# ESP-VINDRIKTNING.net
KiCad netlist of a schematic drawn in EAGLE
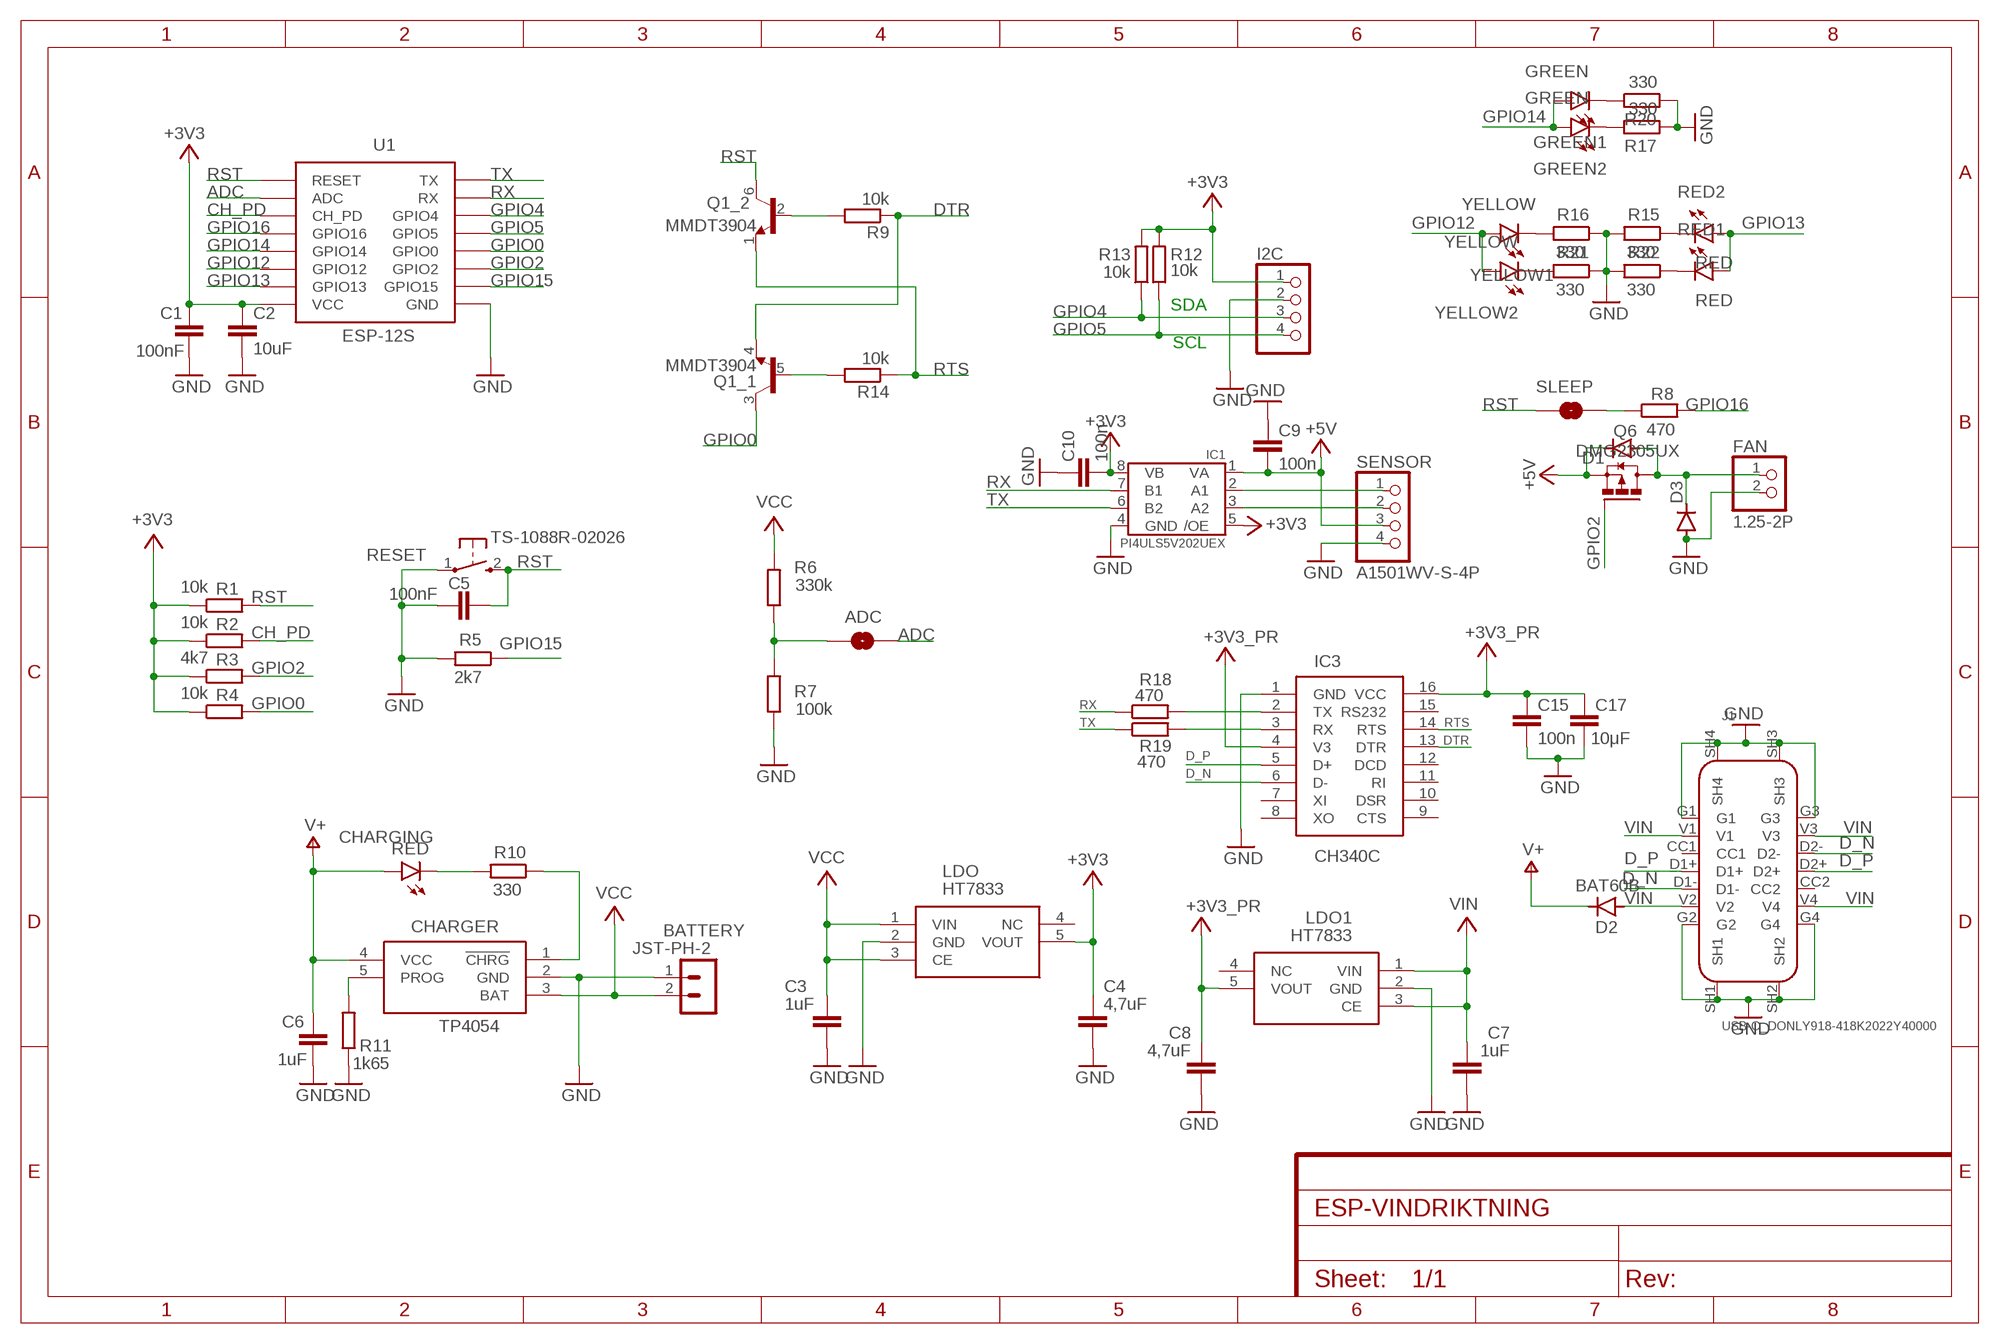
[diagram p0: schematic, sheet 1]

(export (version "E")
  (design (tool "Eeschema 10.0.6"))
  (components
    (comp (ref "ADC")
      (value "JUMPER-SMT_2_NO_NO-SILK")
      (footprint "eagle-import:SMT-JUMPER_2_NO_NO-SILK")
      (libsource (lib "eagle-import") (part "JUMPER-SMT_2_NO_NO-SILK"))
    )
    (comp (ref "BATTERY")
      (value "JST-PH-2")
      (footprint "eagle-import:B2B-PH-K")
      (libsource (lib "eagle-import") (part "JST-PH-2"))
    )
    (comp (ref "C1")
      (value "100nF")
      (footprint "eagle-import:C0603")
      (libsource (lib "eagle-import") (part "C-EUC0603"))
    )
    (comp (ref "C2")
      (value "10uF")
      (footprint "eagle-import:C0603")
      (libsource (lib "eagle-import") (part "C-EUC0603"))
    )
    (comp (ref "C3")
      (value "1uF")
      (footprint "eagle-import:C0603")
      (libsource (lib "eagle-import") (part "C-EUC0603"))
    )
    (comp (ref "C4")
      (value "4,7uF")
      (footprint "eagle-import:C0603")
      (fields (field (name "LCSC_PART") "C50936"))
      (libsource (lib "eagle-import") (part "C-EUC0603"))
    )
    (comp (ref "C5")
      (value "100nF")
      (footprint "eagle-import:C0402")
      (libsource (lib "eagle-import") (part "C-EUC0402"))
    )
    (comp (ref "C6")
      (value "1uF")
      (footprint "eagle-import:C0603")
      (libsource (lib "eagle-import") (part "C-EUC0603"))
    )
    (comp (ref "C7")
      (value "1uF")
      (footprint "eagle-import:C0603")
      (libsource (lib "eagle-import") (part "C-EUC0603"))
    )
    (comp (ref "C8")
      (value "4,7uF")
      (footprint "eagle-import:C0603")
      (fields (field (name "LCSC_PART") "C50936"))
      (libsource (lib "eagle-import") (part "C-EUC0603"))
    )
    (comp (ref "C9")
      (value "100n")
      (footprint "eagle-import:C0603")
      (libsource (lib "eagle-import") (part "C-EUC0603"))
    )
    (comp (ref "C10")
      (value "100n")
      (footprint "eagle-import:C0603")
      (libsource (lib "eagle-import") (part "C-EUC0603"))
    )
    (comp (ref "C15")
      (value "100n")
      (footprint "eagle-import:C0603")
      (libsource (lib "eagle-import") (part "C-EUC0603"))
    )
    (comp (ref "C17")
      (value "10μF")
      (footprint "eagle-import:C0603")
      (libsource (lib "eagle-import") (part "C-EUC0603"))
    )
    (comp (ref "CHARGER")
      (value "TP4054")
      (footprint "eagle-import:SOT-23-5")
      (fields (field (name "ARROW_PART_NUMBER") "TP4054-42-SOT25-R"))
      (libsource (lib "eagle-import") (part "TP4054-42-SOT25-R"))
    )
    (comp (ref "CHARGING")
      (value "RED")
      (footprint "eagle-import:CHIPLED_0603")
      (libsource (lib "eagle-import") (part "LEDCHIPLED_0603"))
    )
    (comp (ref "D1")
      (value "DIODE-SOD323-R")
      (footprint "eagle-import:SOD323-R")
      (libsource (lib "eagle-import") (part "DIODE-SOD323-R"))
    )
    (comp (ref "D2")
      (value "BAT60B")
      (footprint "eagle-import:SOD323-R")
      (libsource (lib "eagle-import") (part "DIODE-SOD323-R"))
    )
    (comp (ref "D3")
      (value "DIODE-SOD323-R")
      (footprint "eagle-import:SOD323-R")
      (libsource (lib "eagle-import") (part "DIODE-SOD323-R"))
    )
    (comp (ref "FAN")
      (value "1.25-2P")
      (footprint "eagle-import:1.25-2P")
      (fields (field (name "LCSC_PART") "C393945"))
      (libsource (lib "eagle-import") (part "1.25-2P"))
    )
    (comp (ref "GREEN1")
      (value "GREEN")
      (footprint "eagle-import:CHIP-LED0603")
      (libsource (lib "eagle-import") (part "LEDCHIP-LED0603"))
    )
    (comp (ref "GREEN2")
      (value "GREEN")
      (footprint "eagle-import:CHIP-LED0603")
      (libsource (lib "eagle-import") (part "LEDCHIP-LED0603"))
    )
    (comp (ref "I2C")
      (value "PINHD-1X4")
      (footprint "eagle-import:1X04")
      (libsource (lib "eagle-import") (part "PINHD-1X4"))
    )
    (comp (ref "IC1")
      (value "PI4ULS5V202UEX")
      (footprint "eagle-import:MSOP8")
      (fields (field (name "LCSC_PART") "C481697"))
      (libsource (lib "eagle-import") (part "PI4ULS5V202UEX"))
    )
    (comp (ref "IC3")
      (value "CH340C")
      (footprint "eagle-import:SOIC16")
      (libsource (lib "eagle-import") (part "USB_UART_CONVERTOR_CH340G"))
    )
    (comp (ref "J1")
      (value "USB-C_DONLY918-418K2022Y40000")
      (footprint "eagle-import:USB-C-TH")
      (fields (field (name "LCSC_PART") "C168704"))
      (libsource (lib "eagle-import") (part "USB-C_DONLY918-418K2022Y40000"))
    )
    (comp (ref "LDO")
      (value "HT7833")
      (footprint "eagle-import:SOT23-5")
      (libsource (lib "eagle-import") (part "HT78XX-SOT23-5SOT23-5"))
    )
    (comp (ref "LDO1")
      (value "HT7833")
      (footprint "eagle-import:SOT23-5")
      (libsource (lib "eagle-import") (part "HT78XX-SOT23-5SOT23-5"))
    )
    (comp (ref "Q1")
      (value "MMDT3904")
      (footprint "eagle-import:SC70-6")
      (fields (field (name "LCSC_PART") "C268586"))
      (libsource (lib "eagle-import") (part "TRANS_NPN_DUAL-MBT3904DW1T1"))
    )
    (comp (ref "Q6")
      (value "DMG2305UX")
      (footprint "eagle-import:SUPER-SOT3")
      (fields (field (name "LCSC_PART") "C144153"))
      (libsource (lib "eagle-import") (part "FDN360P"))
    )
    (comp (ref "R1")
      (value "10k")
      (footprint "eagle-import:R0402")
      (libsource (lib "eagle-import") (part "R-EU_R0402"))
    )
    (comp (ref "R2")
      (value "10k")
      (footprint "eagle-import:R0402")
      (libsource (lib "eagle-import") (part "R-EU_R0402"))
    )
    (comp (ref "R3")
      (value "4k7")
      (footprint "eagle-import:R0402")
      (libsource (lib "eagle-import") (part "R-EU_R0402"))
    )
    (comp (ref "R4")
      (value "10k")
      (footprint "eagle-import:R0402")
      (libsource (lib "eagle-import") (part "R-EU_R0402"))
    )
    (comp (ref "R5")
      (value "2k7")
      (footprint "eagle-import:R0402")
      (libsource (lib "eagle-import") (part "R-EU_R0402"))
    )
    (comp (ref "R6")
      (value "330k")
      (footprint "eagle-import:R0402")
      (libsource (lib "eagle-import") (part "R-EU_R0402"))
    )
    (comp (ref "R7")
      (value "100k")
      (footprint "eagle-import:R0402")
      (libsource (lib "eagle-import") (part "R-EU_R0402"))
    )
    (comp (ref "R8")
      (value "470")
      (footprint "eagle-import:R0402")
      (libsource (lib "eagle-import") (part "R-EU_R0402"))
    )
    (comp (ref "R9")
      (value "10k")
      (footprint "eagle-import:R0402")
      (libsource (lib "eagle-import") (part "R-EU_R0402"))
    )
    (comp (ref "R10")
      (value "330")
      (footprint "eagle-import:R0603")
      (libsource (lib "eagle-import") (part "R-EU_R0603"))
    )
    (comp (ref "R11")
      (value "1k65")
      (footprint "eagle-import:R0603")
      (libsource (lib "eagle-import") (part "R-EU_R0603"))
    )
    (comp (ref "R12")
      (value "10k")
      (footprint "eagle-import:R0402")
      (libsource (lib "eagle-import") (part "R-EU_R0402"))
    )
    (comp (ref "R13")
      (value "10k")
      (footprint "eagle-import:R0402")
      (libsource (lib "eagle-import") (part "R-EU_R0402"))
    )
    (comp (ref "R14")
      (value "10k")
      (footprint "eagle-import:R0402")
      (libsource (lib "eagle-import") (part "R-EU_R0402"))
    )
    (comp (ref "R15")
      (value "330")
      (footprint "eagle-import:R0402")
      (libsource (lib "eagle-import") (part "R-EU_R0402"))
    )
    (comp (ref "R16")
      (value "330")
      (footprint "eagle-import:R0402")
      (libsource (lib "eagle-import") (part "R-EU_R0402"))
    )
    (comp (ref "R17")
      (value "330")
      (footprint "eagle-import:R0402")
      (libsource (lib "eagle-import") (part "R-EU_R0402"))
    )
    (comp (ref "R18")
      (value "470")
      (footprint "eagle-import:R0603")
      (libsource (lib "eagle-import") (part "R-EU_R0603"))
    )
    (comp (ref "R19")
      (value "470")
      (footprint "eagle-import:R0603")
      (libsource (lib "eagle-import") (part "R-EU_R0603"))
    )
    (comp (ref "R20")
      (value "330")
      (footprint "eagle-import:R0402")
      (libsource (lib "eagle-import") (part "R-EU_R0402"))
    )
    (comp (ref "R21")
      (value "330")
      (footprint "eagle-import:R0402")
      (libsource (lib "eagle-import") (part "R-EU_R0402"))
    )
    (comp (ref "R22")
      (value "330")
      (footprint "eagle-import:R0402")
      (libsource (lib "eagle-import") (part "R-EU_R0402"))
    )
    (comp (ref "RED1")
      (value "RED")
      (footprint "eagle-import:CHIP-LED0603")
      (libsource (lib "eagle-import") (part "LEDCHIP-LED0603"))
    )
    (comp (ref "RED2")
      (value "RED")
      (footprint "eagle-import:CHIP-LED0603")
      (libsource (lib "eagle-import") (part "LEDCHIP-LED0603"))
    )
    (comp (ref "RESET")
      (value "TS-1088R-02026")
      (footprint "eagle-import:TS1088R02026")
      (libsource (lib "eagle-import") (part "MOMENTARY_SWITCH_TS-1088R-02026"))
    )
    (comp (ref "SENSOR")
      (value "A1501WV-S-4P")
      (footprint "eagle-import:A1501WV-S-4P")
      (fields (field (name "LCSC_PART") "C225162"))
      (libsource (lib "eagle-import") (part "A1501WV-S-4P"))
    )
    (comp (ref "SLEEP")
      (value "JUMPER-SMT_2_NO_NO-SILK")
      (footprint "eagle-import:SMT-JUMPER_2_NO_NO-SILK")
      (libsource (lib "eagle-import") (part "JUMPER-SMT_2_NO_NO-SILK"))
    )
    (comp (ref "U1")
      (value "ESP-12S")
      (footprint "eagle-import:ESP12-SMD")
      (libsource (lib "eagle-import") (part "WIFI_ESP12SMD"))
    )
    (comp (ref "YELLOW1")
      (value "YELLOW")
      (footprint "eagle-import:CHIP-LED0603")
      (libsource (lib "eagle-import") (part "LEDCHIP-LED0603"))
    )
    (comp (ref "YELLOW2")
      (value "YELLOW")
      (footprint "eagle-import:CHIP-LED0603")
      (libsource (lib "eagle-import") (part "LEDCHIP-LED0603"))
    )
  )
  (nets
    (net (code "1") (name "+3V3") (class "Default")
      (node (ref "C1") (pin "1") (pinfunction "1_1") (pintype "passive"))
      (node (ref "C10") (pin "2") (pinfunction "2_2") (pintype "passive"))
      (node (ref "C2") (pin "1") (pinfunction "1_1") (pintype "passive"))
      (node (ref "C4") (pin "1") (pinfunction "1_1") (pintype "passive"))
      (node (ref "I2C") (pin "1") (pinfunction "1_1") (pintype "passive"))
      (node (ref "IC1") (pin "5") (pinfunction "/OE_5") (pintype "bidirectional"))
      (node (ref "IC1") (pin "8") (pinfunction "VB_8") (pintype "bidirectional"))
      (node (ref "LDO") (pin "5") (pinfunction "VOUT_5") (pintype "bidirectional"))
      (node (ref "R1") (pin "1") (pinfunction "1_1") (pintype "passive"))
      (node (ref "R12") (pin "2") (pinfunction "2_2") (pintype "passive"))
      (node (ref "R13") (pin "2") (pinfunction "2_2") (pintype "passive"))
      (node (ref "R2") (pin "1") (pinfunction "1_1") (pintype "passive"))
      (node (ref "R3") (pin "1") (pinfunction "1_1") (pintype "passive"))
      (node (ref "R4") (pin "1") (pinfunction "1_1") (pintype "passive"))
      (node (ref "U1") (pin "VCC") (pinfunction "VCC_VCC") (pintype "bidirectional"))
    )
    (net (code "2") (name "+3V3_PR") (class "Default")
      (node (ref "C15") (pin "1") (pinfunction "1_1") (pintype "passive"))
      (node (ref "C17") (pin "1") (pinfunction "1_1") (pintype "passive"))
      (node (ref "C8") (pin "1") (pinfunction "1_1") (pintype "passive"))
      (node (ref "IC3") (pin "16") (pinfunction "VCC_16") (pintype "bidirectional"))
      (node (ref "IC3") (pin "4") (pinfunction "V3_4") (pintype "bidirectional"))
      (node (ref "LDO1") (pin "5") (pinfunction "VOUT_5") (pintype "bidirectional"))
    )
    (net (code "3") (name "+5V") (class "Default")
      (node (ref "C9") (pin "2") (pinfunction "2_2") (pintype "passive"))
      (node (ref "D1") (pin "C") (pinfunction "C_C") (pintype "passive"))
      (node (ref "IC1") (pin "1") (pinfunction "VA_1") (pintype "bidirectional"))
      (node (ref "Q6") (pin "2") (pinfunction "S_2") (pintype "passive"))
      (node (ref "SENSOR") (pin "3") (pinfunction "3_3") (pintype "passive"))
    )
    (net (code "4") (name "/ADC") (class "Default")
      (node (ref "ADC") (pin "2") (pinfunction "2_2") (pintype "passive"))
      (node (ref "U1") (pin "ADC") (pinfunction "ADC_ADC") (pintype "bidirectional"))
    )
    (net (code "5") (name "/CH_PD") (class "Default")
      (node (ref "R2") (pin "2") (pinfunction "2_2") (pintype "passive"))
      (node (ref "U1") (pin "CH_PD") (pinfunction "CH_PD_CH_PD") (pintype "bidirectional"))
    )
    (net (code "6") (name "/DTR") (class "Default")
      (node (ref "IC3") (pin "13") (pinfunction "DTR_13") (pintype "bidirectional"))
      (node (ref "Q1") (pin "4") (pinfunction "E_4") (pintype "passive"))
      (node (ref "R9") (pin "1") (pinfunction "1_1") (pintype "passive"))
    )
    (net (code "7") (name "/D_N") (class "Default")
      (node (ref "IC3") (pin "6") (pinfunction "D-_6") (pintype "bidirectional"))
      (node (ref "J1") (pin "D1-") (pinfunction "D1-_D1-") (pintype "bidirectional"))
      (node (ref "J1") (pin "D2-") (pinfunction "D2-_D2-") (pintype "bidirectional"))
    )
    (net (code "8") (name "/D_P") (class "Default")
      (node (ref "IC3") (pin "5") (pinfunction "D+_5") (pintype "bidirectional"))
      (node (ref "J1") (pin "D1+") (pinfunction "D1+_D1+") (pintype "bidirectional"))
      (node (ref "J1") (pin "D2+") (pinfunction "D2+_D2+") (pintype "bidirectional"))
    )
    (net (code "9") (name "/GPIO0") (class "Default")
      (node (ref "Q1") (pin "3") (pinfunction "C_3") (pintype "passive"))
      (node (ref "R4") (pin "2") (pinfunction "2_2") (pintype "passive"))
      (node (ref "U1") (pin "GPIO0") (pinfunction "GPIO0_GPIO0") (pintype "bidirectional"))
    )
    (net (code "10") (name "/GPIO2") (class "Default")
      (node (ref "Q6") (pin "1") (pinfunction "G_1") (pintype "passive"))
      (node (ref "R3") (pin "2") (pinfunction "2_2") (pintype "passive"))
      (node (ref "U1") (pin "GPIO2") (pinfunction "GPIO2_GPIO2") (pintype "bidirectional"))
    )
    (net (code "11") (name "/GPIO4") (class "Default")
      (node (ref "I2C") (pin "3") (pinfunction "3_3") (pintype "passive"))
      (node (ref "R13") (pin "1") (pinfunction "1_1") (pintype "passive"))
      (node (ref "U1") (pin "GPIO4") (pinfunction "GPIO4_GPIO4") (pintype "bidirectional"))
    )
    (net (code "12") (name "/GPIO5") (class "Default")
      (node (ref "I2C") (pin "4") (pinfunction "4_4") (pintype "passive"))
      (node (ref "R12") (pin "1") (pinfunction "1_1") (pintype "passive"))
      (node (ref "U1") (pin "GPIO5") (pinfunction "GPIO5_GPIO5") (pintype "bidirectional"))
    )
    (net (code "13") (name "/GPIO12") (class "Default")
      (node (ref "U1") (pin "GPIO12") (pinfunction "GPIO12_GPIO12") (pintype "bidirectional"))
      (node (ref "YELLOW1") (pin "A") (pinfunction "A_A") (pintype "passive"))
      (node (ref "YELLOW2") (pin "A") (pinfunction "A_A") (pintype "passive"))
    )
    (net (code "14") (name "/GPIO13") (class "Default")
      (node (ref "RED1") (pin "A") (pinfunction "A_A") (pintype "passive"))
      (node (ref "RED2") (pin "A") (pinfunction "A_A") (pintype "passive"))
      (node (ref "U1") (pin "GPIO13") (pinfunction "GPIO13_GPIO13") (pintype "bidirectional"))
    )
    (net (code "15") (name "/GPIO14") (class "Default")
      (node (ref "GREEN1") (pin "A") (pinfunction "A_A") (pintype "passive"))
      (node (ref "GREEN2") (pin "A") (pinfunction "A_A") (pintype "passive"))
      (node (ref "U1") (pin "GPIO14") (pinfunction "GPIO14_GPIO14") (pintype "bidirectional"))
    )
    (net (code "16") (name "/GPIO15") (class "Default")
      (node (ref "R5") (pin "1") (pinfunction "1_1") (pintype "passive"))
      (node (ref "U1") (pin "GPIO15") (pinfunction "GPIO15_GPIO15") (pintype "bidirectional"))
    )
    (net (code "17") (name "/GPIO16") (class "Default")
      (node (ref "R8") (pin "2") (pinfunction "2_2") (pintype "passive"))
      (node (ref "U1") (pin "GPIO16") (pinfunction "GPIO16_GPIO16") (pintype "bidirectional"))
    )
    (net (code "18") (name "/RST") (class "Default")
      (node (ref "C5") (pin "2") (pinfunction "2_2") (pintype "passive"))
      (node (ref "Q1") (pin "6") (pinfunction "C_6") (pintype "passive"))
      (node (ref "R1") (pin "2") (pinfunction "2_2") (pintype "passive"))
      (node (ref "RESET") (pin "2") (pinfunction "3_2") (pintype "passive"))
      (node (ref "SLEEP") (pin "1") (pinfunction "1_1") (pintype "passive"))
      (node (ref "U1") (pin "RESET") (pinfunction "RESET_RESET") (pintype "bidirectional"))
    )
    (net (code "19") (name "/RTS") (class "Default")
      (node (ref "IC3") (pin "14") (pinfunction "RTS_14") (pintype "bidirectional"))
      (node (ref "Q1") (pin "1") (pinfunction "E_1") (pintype "passive"))
      (node (ref "R14") (pin "1") (pinfunction "1_1") (pintype "passive"))
    )
    (net (code "20") (name "/RX") (class "Default")
      (node (ref "IC1") (pin "7") (pinfunction "B1_7") (pintype "bidirectional"))
      (node (ref "R18") (pin "1") (pinfunction "1_1") (pintype "passive"))
      (node (ref "U1") (pin "RXD0") (pinfunction "RX_RXD0") (pintype "bidirectional"))
    )
    (net (code "21") (name "/TX") (class "Default")
      (node (ref "IC1") (pin "6") (pinfunction "B2_6") (pintype "bidirectional"))
      (node (ref "R19") (pin "1") (pinfunction "1_1") (pintype "passive"))
      (node (ref "U1") (pin "TXD0") (pinfunction "TX_TXD0") (pintype "bidirectional"))
    )
    (net (code "22") (name "GND") (class "Default")
      (node (ref "BATTERY") (pin "1") (pinfunction "2_1") (pintype "passive"))
      (node (ref "C1") (pin "2") (pinfunction "2_2") (pintype "passive"))
      (node (ref "C10") (pin "1") (pinfunction "1_1") (pintype "passive"))
      (node (ref "C15") (pin "2") (pinfunction "2_2") (pintype "passive"))
      (node (ref "C17") (pin "2") (pinfunction "2_2") (pintype "passive"))
      (node (ref "C2") (pin "2") (pinfunction "2_2") (pintype "passive"))
      (node (ref "C3") (pin "2") (pinfunction "2_2") (pintype "passive"))
      (node (ref "C4") (pin "2") (pinfunction "2_2") (pintype "passive"))
      (node (ref "C5") (pin "1") (pinfunction "1_1") (pintype "passive"))
      (node (ref "C6") (pin "2") (pinfunction "2_2") (pintype "passive"))
      (node (ref "C7") (pin "2") (pinfunction "2_2") (pintype "passive"))
      (node (ref "C8") (pin "2") (pinfunction "2_2") (pintype "passive"))
      (node (ref "C9") (pin "1") (pinfunction "1_1") (pintype "passive"))
      (node (ref "CHARGER") (pin "2") (pinfunction "GND_2") (pintype "bidirectional"))
      (node (ref "D3") (pin "A") (pinfunction "A_A") (pintype "passive"))
      (node (ref "FAN") (pin "2") (pinfunction "2_2") (pintype "passive"))
      (node (ref "I2C") (pin "2") (pinfunction "2_2") (pintype "passive"))
      (node (ref "IC1") (pin "4") (pinfunction "GND_4") (pintype "bidirectional"))
      (node (ref "IC3") (pin "1") (pinfunction "GND_1") (pintype "bidirectional"))
      (node (ref "J1") (pin "G1") (pinfunction "G1_G1") (pintype "bidirectional"))
      (node (ref "J1") (pin "G2") (pinfunction "G2_G2") (pintype "bidirectional"))
      (node (ref "J1") (pin "G3") (pinfunction "G3_G3") (pintype "bidirectional"))
      (node (ref "J1") (pin "G4") (pinfunction "G4_G4") (pintype "bidirectional"))
      (node (ref "J1") (pin "SH1") (pinfunction "SH1_SH1") (pintype "bidirectional"))
      (node (ref "J1") (pin "SH2") (pinfunction "SH2_SH2") (pintype "bidirectional"))
      (node (ref "J1") (pin "SH3") (pinfunction "SH3_SH3") (pintype "bidirectional"))
      (node (ref "J1") (pin "SH4") (pinfunction "SH4_SH4") (pintype "bidirectional"))
      (node (ref "LDO") (pin "2") (pinfunction "GND_2") (pintype "bidirectional"))
      (node (ref "LDO1") (pin "2") (pinfunction "GND_2") (pintype "bidirectional"))
      (node (ref "R11") (pin "1") (pinfunction "1_1") (pintype "passive"))
      (node (ref "R15") (pin "2") (pinfunction "2_2") (pintype "passive"))
      (node (ref "R16") (pin "1") (pinfunction "1_1") (pintype "passive"))
      (node (ref "R17") (pin "2") (pinfunction "2_2") (pintype "passive"))
      (node (ref "R20") (pin "2") (pinfunction "2_2") (pintype "passive"))
      (node (ref "R21") (pin "1") (pinfunction "1_1") (pintype "passive"))
      (node (ref "R22") (pin "2") (pinfunction "2_2") (pintype "passive"))
      (node (ref "R5") (pin "2") (pinfunction "2_2") (pintype "passive"))
      (node (ref "R7") (pin "1") (pinfunction "1_1") (pintype "passive"))
      (node (ref "RESET") (pin "1") (pinfunction "1_1") (pintype "passive"))
      (node (ref "SENSOR") (pin "4") (pinfunction "4_4") (pintype "passive"))
      (node (ref "U1") (pin "GND") (pinfunction "GND_GND") (pintype "bidirectional"))
    )
    (net (code "23") (name "Net-(ADC-Pad1)") (class "Default")
      (node (ref "ADC") (pin "1") (pinfunction "1_1") (pintype "passive"))
      (node (ref "R6") (pin "1") (pinfunction "1_1") (pintype "passive"))
      (node (ref "R7") (pin "2") (pinfunction "2_2") (pintype "passive"))
    )
    (net (code "24") (name "Net-(CHARGER-PROG)") (class "Default")
      (node (ref "CHARGER") (pin "5") (pinfunction "PROG_5") (pintype "bidirectional"))
      (node (ref "R11") (pin "2") (pinfunction "2_2") (pintype "passive"))
    )
    (net (code "25") (name "Net-(CHARGER-~{CHRG})") (class "Default")
      (node (ref "CHARGER") (pin "1") (pinfunction "~{CHRG}_1") (pintype "bidirectional"))
      (node (ref "R10") (pin "1") (pinfunction "1_1") (pintype "passive"))
    )
    (net (code "26") (name "Net-(CHARGING-PadC)") (class "Default")
      (node (ref "CHARGING") (pin "C") (pinfunction "C_C") (pintype "passive"))
      (node (ref "R10") (pin "2") (pinfunction "2_2") (pintype "passive"))
    )
    (net (code "27") (name "Net-(GREEN1-PadC)") (class "Default")
      (node (ref "GREEN1") (pin "C") (pinfunction "C_C") (pintype "passive"))
      (node (ref "R20") (pin "1") (pinfunction "1_1") (pintype "passive"))
    )
    (net (code "28") (name "Net-(GREEN2-PadC)") (class "Default")
      (node (ref "GREEN2") (pin "C") (pinfunction "C_C") (pintype "passive"))
      (node (ref "R17") (pin "1") (pinfunction "1_1") (pintype "passive"))
    )
    (net (code "29") (name "Net-(IC1-A1)") (class "Default")
      (node (ref "IC1") (pin "2") (pinfunction "A1_2") (pintype "bidirectional"))
      (node (ref "SENSOR") (pin "1") (pinfunction "1_1") (pintype "passive"))
    )
    (net (code "30") (name "Net-(IC1-A2)") (class "Default")
      (node (ref "IC1") (pin "3") (pinfunction "A2_3") (pintype "bidirectional"))
      (node (ref "SENSOR") (pin "2") (pinfunction "2_2") (pintype "passive"))
    )
    (net (code "31") (name "Net-(IC3-RX)") (class "Default")
      (node (ref "IC3") (pin "3") (pinfunction "RX_3") (pintype "bidirectional"))
      (node (ref "R19") (pin "2") (pinfunction "2_2") (pintype "passive"))
    )
    (net (code "32") (name "Net-(IC3-TX)") (class "Default")
      (node (ref "IC3") (pin "2") (pinfunction "TX_2") (pintype "bidirectional"))
      (node (ref "R18") (pin "2") (pinfunction "2_2") (pintype "passive"))
    )
    (net (code "33") (name "Net-(Q1A-B)") (class "Default")
      (node (ref "Q1") (pin "5") (pinfunction "B_5") (pintype "passive"))
      (node (ref "R14") (pin "2") (pinfunction "2_2") (pintype "passive"))
    )
    (net (code "34") (name "Net-(Q1B-B)") (class "Default")
      (node (ref "Q1") (pin "2") (pinfunction "B_2") (pintype "passive"))
      (node (ref "R9") (pin "2") (pinfunction "2_2") (pintype "passive"))
    )
    (net (code "35") (name "Net-(Q6-D)") (class "Default")
      (node (ref "D1") (pin "A") (pinfunction "A_A") (pintype "passive"))
      (node (ref "D3") (pin "C") (pinfunction "C_C") (pintype "passive"))
      (node (ref "FAN") (pin "1") (pinfunction "1_1") (pintype "passive"))
      (node (ref "Q6") (pin "3") (pinfunction "D_3") (pintype "passive"))
    )
    (net (code "36") (name "Net-(R8-Pad1)") (class "Default")
      (node (ref "R8") (pin "1") (pinfunction "1_1") (pintype "passive"))
      (node (ref "SLEEP") (pin "2") (pinfunction "2_2") (pintype "passive"))
    )
    (net (code "37") (name "Net-(R15-Pad1)") (class "Default")
      (node (ref "R15") (pin "1") (pinfunction "1_1") (pintype "passive"))
      (node (ref "RED2") (pin "C") (pinfunction "C_C") (pintype "passive"))
    )
    (net (code "38") (name "Net-(R16-Pad2)") (class "Default")
      (node (ref "R16") (pin "2") (pinfunction "2_2") (pintype "passive"))
      (node (ref "YELLOW1") (pin "C") (pinfunction "C_C") (pintype "passive"))
    )
    (net (code "39") (name "Net-(R21-Pad2)") (class "Default")
      (node (ref "R21") (pin "2") (pinfunction "2_2") (pintype "passive"))
      (node (ref "YELLOW2") (pin "C") (pinfunction "C_C") (pintype "passive"))
    )
    (net (code "40") (name "Net-(R22-Pad1)") (class "Default")
      (node (ref "R22") (pin "1") (pinfunction "1_1") (pintype "passive"))
      (node (ref "RED1") (pin "C") (pinfunction "C_C") (pintype "passive"))
    )
    (net (code "41") (name "V+") (class "Default")
      (node (ref "C6") (pin "1") (pinfunction "1_1") (pintype "passive"))
      (node (ref "CHARGER") (pin "4") (pinfunction "VCC_4") (pintype "bidirectional"))
      (node (ref "CHARGING") (pin "A") (pinfunction "A_A") (pintype "passive"))
      (node (ref "D2") (pin "C") (pinfunction "C_C") (pintype "passive"))
    )
    (net (code "42") (name "VCC") (class "Default")
      (node (ref "BATTERY") (pin "2") (pinfunction "1_2") (pintype "passive"))
      (node (ref "C3") (pin "1") (pinfunction "1_1") (pintype "passive"))
      (node (ref "CHARGER") (pin "3") (pinfunction "BAT_3") (pintype "bidirectional"))
      (node (ref "LDO") (pin "1") (pinfunction "VIN_1") (pintype "bidirectional"))
      (node (ref "LDO") (pin "3") (pinfunction "CE_3") (pintype "bidirectional"))
      (node (ref "R6") (pin "2") (pinfunction "2_2") (pintype "passive"))
    )
    (net (code "43") (name "VIN") (class "Default")
      (node (ref "C7") (pin "1") (pinfunction "1_1") (pintype "passive"))
      (node (ref "D2") (pin "A") (pinfunction "A_A") (pintype "passive"))
      (node (ref "J1") (pin "V1") (pinfunction "V1_V1") (pintype "bidirectional"))
      (node (ref "J1") (pin "V2") (pinfunction "V2_V2") (pintype "bidirectional"))
      (node (ref "J1") (pin "V3") (pinfunction "V3_V3") (pintype "bidirectional"))
      (node (ref "J1") (pin "V4") (pinfunction "V4_V4") (pintype "bidirectional"))
      (node (ref "LDO1") (pin "1") (pinfunction "VIN_1") (pintype "bidirectional"))
      (node (ref "LDO1") (pin "3") (pinfunction "CE_3") (pintype "bidirectional"))
    )
    (net (code "44") (name "unconnected-(IC3-CTS-Pad9)") (class "Default")
      (node (ref "IC3") (pin "9") (pinfunction "CTS_9") (pintype "bidirectional"))
    )
    (net (code "45") (name "unconnected-(IC3-DCD-Pad12)") (class "Default")
      (node (ref "IC3") (pin "12") (pinfunction "DCD_12") (pintype "bidirectional"))
    )
    (net (code "46") (name "unconnected-(IC3-DSR-Pad10)") (class "Default")
      (node (ref "IC3") (pin "10") (pinfunction "DSR_10") (pintype "bidirectional"))
    )
    (net (code "47") (name "unconnected-(IC3-RI-Pad11)") (class "Default")
      (node (ref "IC3") (pin "11") (pinfunction "RI_11") (pintype "bidirectional"))
    )
    (net (code "48") (name "unconnected-(IC3-RS232-Pad15)") (class "Default")
      (node (ref "IC3") (pin "15") (pinfunction "RS232_15") (pintype "bidirectional"))
    )
    (net (code "49") (name "unconnected-(IC3-XI-Pad7)") (class "Default")
      (node (ref "IC3") (pin "7") (pinfunction "XI_7") (pintype "bidirectional"))
    )
    (net (code "50") (name "unconnected-(IC3-XO-Pad8)") (class "Default")
      (node (ref "IC3") (pin "8") (pinfunction "XO_8") (pintype "bidirectional"))
    )
    (net (code "51") (name "unconnected-(J1-PadCC1)") (class "Default")
      (node (ref "J1") (pin "CC1") (pinfunction "CC1_CC1") (pintype "bidirectional"))
    )
    (net (code "52") (name "unconnected-(J1-PadCC2)") (class "Default")
      (node (ref "J1") (pin "CC2") (pinfunction "CC2_CC2") (pintype "bidirectional"))
    )
    (net (code "53") (name "unconnected-(LDO-NC-Pad4)") (class "Default")
      (node (ref "LDO") (pin "4") (pinfunction "NC_4") (pintype "no_connect"))
    )
    (net (code "54") (name "unconnected-(LDO1-NC-Pad4)") (class "Default")
      (node (ref "LDO1") (pin "4") (pinfunction "NC_4") (pintype "no_connect"))
    )
  )
)
